# MR-71_RE0.net
KiCad netlist of a schematic drawn in Altium Designer
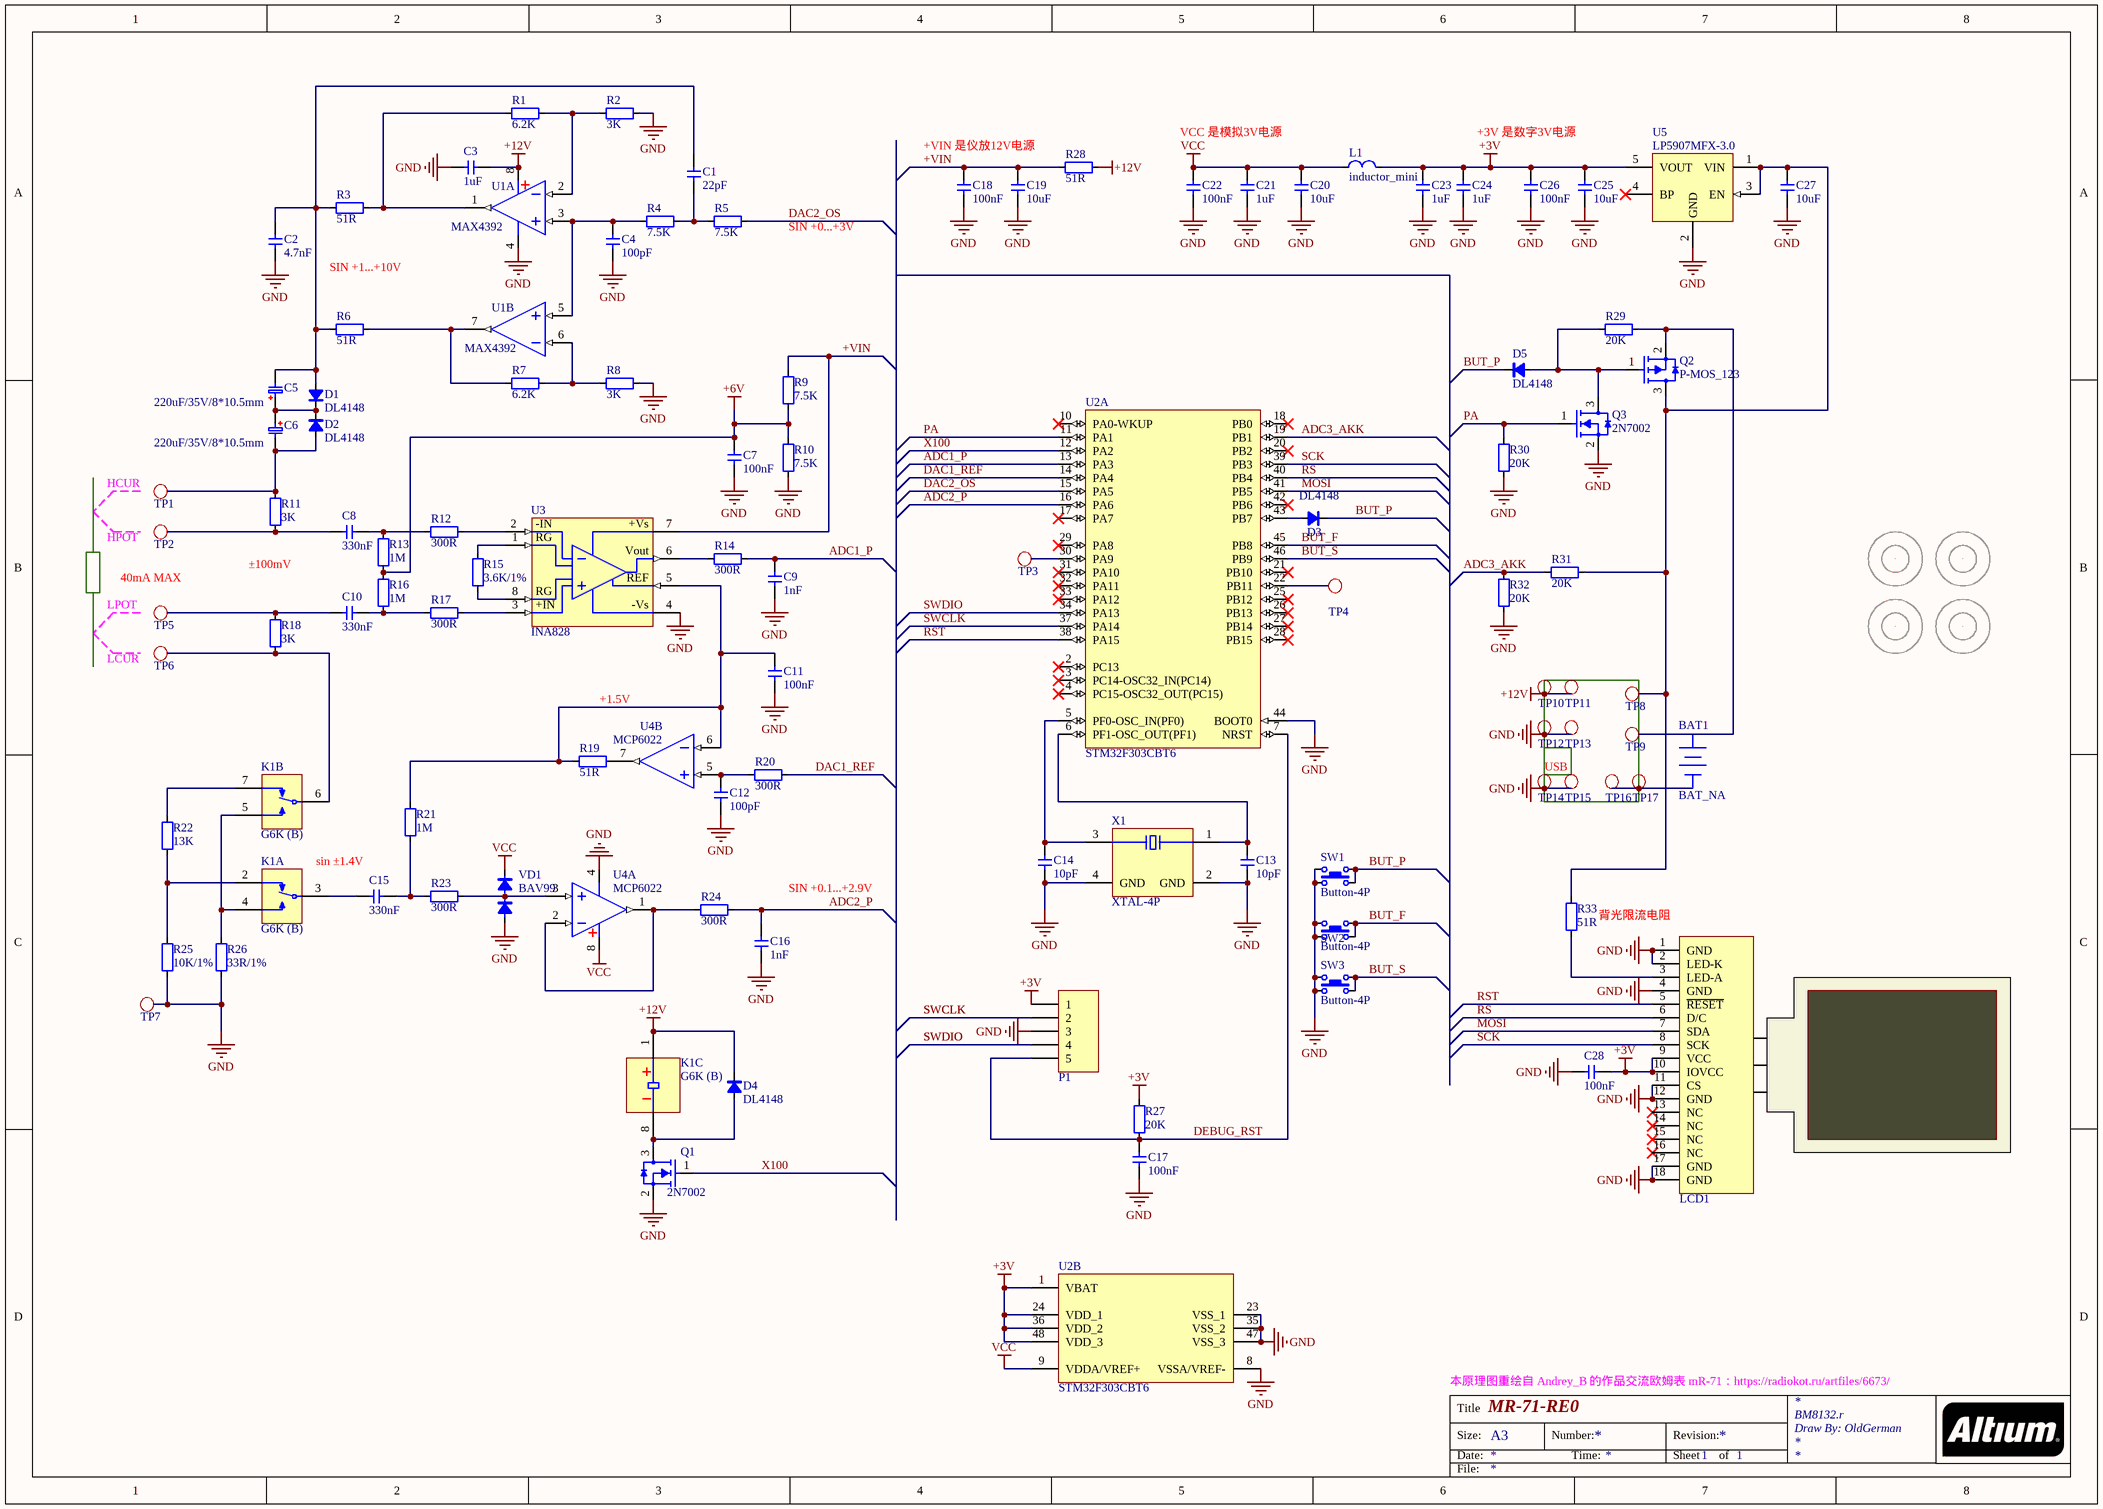
[diagram p0: MR-71_RE0.SchDoc]

(export (version "E")
  (design (tool "Eeschema 10.0.6"))
  (components
    (comp (ref "BAT1")
      (value "BAT_NA")
      (footprint "Lipo_NONE")
      (description "锂电池")
      (libsource (lib "ODG_AD_Lib") (part "BAT_NA"))
    )
    (comp (ref "C1")
      (value "22pF")
      (footprint "C0805")
      (description "Capacitor")
      (libsource (lib "ODG_AD_Lib") (part "CAP"))
    )
    (comp (ref "C2")
      (value "4.7nF")
      (footprint "C0805")
      (description "Capacitor")
      (libsource (lib "ODG_AD_Lib") (part "CAP"))
    )
    (comp (ref "C3")
      (value "1uF")
      (footprint "C0805")
      (description "Capacitor")
      (libsource (lib "ODG_AD_Lib") (part "CAP"))
    )
    (comp (ref "C4")
      (value "100pF")
      (footprint "C0805")
      (description "Capacitor")
      (libsource (lib "ODG_AD_Lib") (part "CAP"))
    )
    (comp (ref "C5")
      (value "220uF/35V/8*10.5mm")
      (footprint "CAP OS-CON D=8.0 L=11.9 E12")
      (description "Capacitor")
      (libsource (lib "ODG_AD_Lib") (part "CAP_Polar_Aluminum"))
    )
    (comp (ref "C6")
      (value "220uF/35V/8*10.5mm")
      (footprint "CAP OS-CON D=8.0 L=11.9 E12")
      (description "Capacitor")
      (libsource (lib "ODG_AD_Lib") (part "CAP_Polar_Aluminum"))
    )
    (comp (ref "C7")
      (value "100nF")
      (footprint "C0805")
      (description "Capacitor")
      (libsource (lib "ODG_AD_Lib") (part "CAP"))
    )
    (comp (ref "C8")
      (value "330nF")
      (footprint "C0805")
      (description "Capacitor")
      (libsource (lib "ODG_AD_Lib") (part "CAP"))
    )
    (comp (ref "C9")
      (value "1nF")
      (footprint "C0805")
      (description "Capacitor")
      (libsource (lib "ODG_AD_Lib") (part "CAP"))
    )
    (comp (ref "C10")
      (value "330nF")
      (footprint "C0805")
      (description "Capacitor")
      (libsource (lib "ODG_AD_Lib") (part "CAP"))
    )
    (comp (ref "C11")
      (value "100nF")
      (footprint "C0805")
      (description "Capacitor")
      (libsource (lib "ODG_AD_Lib") (part "CAP"))
    )
    (comp (ref "C12")
      (value "100pF")
      (footprint "C0805")
      (description "Capacitor")
      (libsource (lib "ODG_AD_Lib") (part "CAP"))
    )
    (comp (ref "C13")
      (value "10pF")
      (footprint "C0805")
      (description "Capacitor")
      (libsource (lib "ODG_AD_Lib") (part "CAP"))
    )
    (comp (ref "C14")
      (value "10pF")
      (footprint "C0805")
      (description "Capacitor")
      (libsource (lib "ODG_AD_Lib") (part "CAP"))
    )
    (comp (ref "C15")
      (value "330nF")
      (footprint "C0805")
      (description "Capacitor")
      (libsource (lib "ODG_AD_Lib") (part "CAP"))
    )
    (comp (ref "C16")
      (value "1nF")
      (footprint "C0805")
      (description "Capacitor")
      (libsource (lib "ODG_AD_Lib") (part "CAP"))
    )
    (comp (ref "C17")
      (value "100nF")
      (footprint "C0805")
      (description "Capacitor")
      (libsource (lib "ODG_AD_Lib") (part "CAP"))
    )
    (comp (ref "C18")
      (value "100nF")
      (footprint "C0805")
      (description "Capacitor")
      (libsource (lib "ODG_AD_Lib") (part "CAP"))
    )
    (comp (ref "C19")
      (value "10uF")
      (footprint "C1206")
      (description "Capacitor")
      (libsource (lib "ODG_AD_Lib") (part "CAP"))
    )
    (comp (ref "C20")
      (value "10uF")
      (footprint "C1206")
      (description "Capacitor")
      (libsource (lib "ODG_AD_Lib") (part "CAP"))
    )
    (comp (ref "C21")
      (value "1uF")
      (footprint "C0805")
      (description "Capacitor")
      (libsource (lib "ODG_AD_Lib") (part "CAP"))
    )
    (comp (ref "C22")
      (value "100nF")
      (footprint "C0805")
      (description "Capacitor")
      (libsource (lib "ODG_AD_Lib") (part "CAP"))
    )
    (comp (ref "C23")
      (value "1uF")
      (footprint "C0805")
      (description "Capacitor")
      (libsource (lib "ODG_AD_Lib") (part "CAP"))
    )
    (comp (ref "C24")
      (value "1uF")
      (footprint "C0805")
      (description "Capacitor")
      (libsource (lib "ODG_AD_Lib") (part "CAP"))
    )
    (comp (ref "C25")
      (value "10uF")
      (footprint "C1206")
      (description "Capacitor")
      (libsource (lib "ODG_AD_Lib") (part "CAP"))
    )
    (comp (ref "C26")
      (value "100nF")
      (footprint "C0805")
      (description "Capacitor")
      (libsource (lib "ODG_AD_Lib") (part "CAP"))
    )
    (comp (ref "C27")
      (value "10uF")
      (footprint "C1206")
      (description "Capacitor")
      (libsource (lib "ODG_AD_Lib") (part "CAP"))
    )
    (comp (ref "C28")
      (value "100nF")
      (footprint "C0805")
      (description "Capacitor")
      (libsource (lib "ODG_AD_Lib") (part "CAP"))
    )
    (comp (ref "D1")
      (value "DL4148")
      (footprint "SOD-123")
      (description "二极管")
      (libsource (lib "ODG_AD_Lib") (part "DIODE"))
    )
    (comp (ref "D2")
      (value "DL4148")
      (footprint "SOD-123")
      (description "二极管")
      (libsource (lib "") (part "DIODE_3"))
    )
    (comp (ref "D3")
      (value "DL4148")
      (footprint "SOD-123")
      (description "二极管")
      (libsource (lib "") (part "DIODE_1"))
    )
    (comp (ref "D4")
      (value "DL4148")
      (footprint "SOD-123")
      (description "二极管")
      (libsource (lib "") (part "DIODE_3"))
    )
    (comp (ref "D5")
      (value "DL4148")
      (footprint "SOD-123")
      (description "二极管")
      (libsource (lib "") (part "DIODE_2"))
    )
    (comp (ref "H1") (value "HOLE") (footprint "M3.1 D=5.8 SUN") (libsource (lib "ODG_AD_Lib") (part "HOLE")))
    (comp (ref "H2") (value "HOLE") (footprint "M3.1 D=5.8 SUN") (libsource (lib "ODG_AD_Lib") (part "HOLE")))
    (comp (ref "H3") (value "HOLE") (footprint "M3.1 D=5.8 SUN") (libsource (lib "ODG_AD_Lib") (part "HOLE")))
    (comp (ref "H4") (value "HOLE") (footprint "M3.1 D=5.8 SUN") (libsource (lib "ODG_AD_Lib") (part "HOLE")))
    (comp (ref "K1")
      (value "G6K (B)")
      (footprint "RELAY_G6K-2F-Y")
      (description "Telecom Relay DPDT (2 Form C) Surface Mount")
      (fields (field (name "MF") "Omron Electronics") (field (name "MP") "G6K-2F DC3"))
      (libsource (lib "") (part "G6K (B)_1"))
    )
    (comp (ref "L1")
      (value "inductor_mini")
      (footprint "FER0805")
      (description "贴片叠层电感")
      (libsource (lib "ODG_AD_Lib") (part "inductor_mini"))
    )
    (comp (ref "LCD1")
      (value "LCD_Universal_128x160_18pin")
      (footprint "LCD-128X160-1.8INCH_SOLDER_MR-71")
      (libsource (lib "ODG_AD_Lib") (part "LCD_Universal_128x160_18pin"))
    )
    (comp (ref "P1")
      (value "CONN_X5")
      (footprint "2.54MM_MALE_X5")
      (libsource (lib "ODG_AD_Lib") (part "CONN_X5"))
    )
    (comp (ref "Q1")
      (value "2N7002")
      (footprint "INFINEON SOT-23-3")
      (description "N-MOS")
      (libsource (lib "ODG_AD_Lib") (part "N-MOS_123"))
    )
    (comp (ref "Q2")
      (value "P-MOS_123")
      (footprint "INFINEON SOT-23-3")
      (description "P-MOS")
      (libsource (lib "ODG_AD_Lib") (part "P-MOS_123"))
    )
    (comp (ref "Q3")
      (value "2N7002")
      (footprint "INFINEON SOT-23-3")
      (description "N-MOS")
      (libsource (lib "ODG_AD_Lib") (part "N-MOS_123"))
    )
    (comp (ref "R1")
      (value "6.2K")
      (footprint "R0805")
      (description "IEC Standard")
      (libsource (lib "") (part "RES_1"))
    )
    (comp (ref "R2")
      (value "3K")
      (footprint "R0805")
      (description "IEC Standard")
      (libsource (lib "") (part "RES_1"))
    )
    (comp (ref "R3")
      (value "51R")
      (footprint "R0805")
      (description "IEC Standard")
      (libsource (lib "") (part "RES_1"))
    )
    (comp (ref "R4")
      (value "7.5K")
      (footprint "R0805")
      (description "IEC Standard")
      (libsource (lib "") (part "RES_1"))
    )
    (comp (ref "R5")
      (value "7.5K")
      (footprint "R0805")
      (description "IEC Standard")
      (libsource (lib "") (part "RES_1"))
    )
    (comp (ref "R6")
      (value "51R")
      (footprint "R0805")
      (description "IEC Standard")
      (libsource (lib "") (part "RES_2"))
    )
    (comp (ref "R7")
      (value "6.2K")
      (footprint "R0805")
      (description "IEC Standard")
      (libsource (lib "") (part "RES_2"))
    )
    (comp (ref "R8")
      (value "3K")
      (footprint "R0805")
      (description "IEC Standard")
      (libsource (lib "") (part "RES_2"))
    )
    (comp (ref "R9")
      (value "7.5K")
      (footprint "R0805")
      (description "IEC Standard")
      (libsource (lib "") (part "RES_2"))
    )
    (comp (ref "R10")
      (value "7.5K")
      (footprint "R0805")
      (description "IEC Standard")
      (libsource (lib "") (part "RES_2"))
    )
    (comp (ref "R11")
      (value "3K")
      (footprint "R0805")
      (description "IEC Standard")
      (libsource (lib "ODG_AD_Lib") (part "RES"))
    )
    (comp (ref "R12")
      (value "300R")
      (footprint "R0805")
      (description "IEC Standard")
      (libsource (lib "") (part "RES_3"))
    )
    (comp (ref "R13")
      (value "1M")
      (footprint "R0805")
      (description "IEC Standard")
      (libsource (lib "ODG_AD_Lib") (part "RES"))
    )
    (comp (ref "R14")
      (value "300R")
      (footprint "R0805")
      (description "IEC Standard")
      (libsource (lib "") (part "RES_3"))
    )
    (comp (ref "R15")
      (value "3.6K/1%")
      (footprint "R0805")
      (description "IEC Standard")
      (libsource (lib "ODG_AD_Lib") (part "RES"))
    )
    (comp (ref "R16")
      (value "1M")
      (footprint "R0805")
      (description "IEC Standard")
      (libsource (lib "ODG_AD_Lib") (part "RES"))
    )
    (comp (ref "R17")
      (value "300R")
      (footprint "R0805")
      (description "IEC Standard")
      (libsource (lib "") (part "RES_3"))
    )
    (comp (ref "R18")
      (value "3K")
      (footprint "R0805")
      (description "IEC Standard")
      (libsource (lib "ODG_AD_Lib") (part "RES"))
    )
    (comp (ref "R19")
      (value "51R")
      (footprint "R0805")
      (description "IEC Standard")
      (libsource (lib "") (part "RES_2"))
    )
    (comp (ref "R20")
      (value "300R")
      (footprint "R0805")
      (description "IEC Standard")
      (libsource (lib "") (part "RES_3"))
    )
    (comp (ref "R21")
      (value "1M")
      (footprint "R0805")
      (description "IEC Standard")
      (libsource (lib "ODG_AD_Lib") (part "RES"))
    )
    (comp (ref "R22")
      (value "13K")
      (footprint "R0805")
      (description "IEC Standard")
      (libsource (lib "ODG_AD_Lib") (part "RES"))
    )
    (comp (ref "R23")
      (value "300R")
      (footprint "R0805")
      (description "IEC Standard")
      (libsource (lib "") (part "RES_3"))
    )
    (comp (ref "R24")
      (value "300R")
      (footprint "R0805")
      (description "IEC Standard")
      (libsource (lib "") (part "RES_3"))
    )
    (comp (ref "R25")
      (value "10K/1%")
      (footprint "R0805")
      (description "IEC Standard")
      (libsource (lib "ODG_AD_Lib") (part "RES"))
    )
    (comp (ref "R26")
      (value "33R/1%")
      (footprint "R1206")
      (description "IEC Standard")
      (libsource (lib "ODG_AD_Lib") (part "RES"))
    )
    (comp (ref "R27")
      (value "20K")
      (footprint "R0805")
      (description "IEC Standard")
      (libsource (lib "") (part "RES_1"))
    )
    (comp (ref "R28")
      (value "51R")
      (footprint "R0805")
      (description "IEC Standard")
      (libsource (lib "") (part "RES_2"))
    )
    (comp (ref "R29")
      (value "20K")
      (footprint "R0805")
      (description "IEC Standard")
      (libsource (lib "") (part "RES_2"))
    )
    (comp (ref "R30")
      (value "20K")
      (footprint "R0805")
      (description "IEC Standard")
      (libsource (lib "ODG_AD_Lib") (part "RES"))
    )
    (comp (ref "R31")
      (value "20K")
      (footprint "R0805")
      (description "IEC Standard")
      (libsource (lib "") (part "RES_2"))
    )
    (comp (ref "R32")
      (value "20K")
      (footprint "R0805")
      (description "IEC Standard")
      (libsource (lib "ODG_AD_Lib") (part "RES"))
    )
    (comp (ref "R33")
      (value "51R")
      (footprint "R0805")
      (description "IEC Standard")
      (libsource (lib "") (part "RES_1"))
    )
    (comp (ref "SW1")
      (value "Button-4P")
      (footprint "TACTILE_SWITCH_SMD_4X4MM")
      (description "Button")
      (libsource (lib "ODG_AD_Lib") (part "Button-4P"))
    )
    (comp (ref "SW2")
      (value "Button-4P")
      (footprint "TACTILE_SWITCH_SMD_4X4MM")
      (description "Button")
      (libsource (lib "ODG_AD_Lib") (part "Button-4P"))
    )
    (comp (ref "SW3")
      (value "Button-4P")
      (footprint "TACTILE_SWITCH_SMD_4X4MM")
      (description "Button")
      (libsource (lib "ODG_AD_Lib") (part "Button-4P"))
    )
    (comp (ref "TP1")
      (value "TP_SMD")
      (footprint "TP_SMD_1.5mm_01")
      (description "SMD testpad")
      (libsource (lib "ODG_AD_Lib") (part "TP_SMD"))
    )
    (comp (ref "TP2")
      (value "TP_SMD")
      (footprint "TP_SMD_1.5mm_01")
      (description "SMD testpad")
      (libsource (lib "ODG_AD_Lib") (part "TP_SMD"))
    )
    (comp (ref "TP3")
      (value "TP_SMD")
      (footprint "TP_SMD_1.5mm_01")
      (description "SMD testpad")
      (libsource (lib "ODG_AD_Lib") (part "TP_SMD"))
    )
    (comp (ref "TP4")
      (value "TP_SMD")
      (footprint "TP_SMD_1.5mm_01")
      (description "SMD testpad")
      (libsource (lib "ODG_AD_Lib") (part "TP_SMD"))
    )
    (comp (ref "TP5")
      (value "TP_SMD")
      (footprint "TP_SMD_1.5mm_01")
      (description "SMD testpad")
      (libsource (lib "ODG_AD_Lib") (part "TP_SMD"))
    )
    (comp (ref "TP6")
      (value "TP_SMD")
      (footprint "TP_SMD_1.5mm_01")
      (description "SMD testpad")
      (libsource (lib "ODG_AD_Lib") (part "TP_SMD"))
    )
    (comp (ref "TP7")
      (value "TP_SMD")
      (footprint "TP_SMD_1.5mm_01")
      (description "SMD testpad")
      (libsource (lib "ODG_AD_Lib") (part "TP_SMD"))
    )
    (comp (ref "TP8")
      (value "TP_SMD")
      (footprint "TP_SMD_1.5mm_01")
      (description "SMD testpad")
      (libsource (lib "ODG_AD_Lib") (part "TP_SMD"))
    )
    (comp (ref "TP9")
      (value "TP_SMD")
      (footprint "TP_SMD_1.5mm_01")
      (description "SMD testpad")
      (libsource (lib "ODG_AD_Lib") (part "TP_SMD"))
    )
    (comp (ref "TP10")
      (value "TP_SMD")
      (footprint "KEYSTONE_5015")
      (description "SMD testpad")
      (libsource (lib "ODG_AD_Lib") (part "TP_SMD"))
    )
    (comp (ref "TP11")
      (value "TP_SMD")
      (footprint "KEYSTONE_5015")
      (description "SMD testpad")
      (libsource (lib "ODG_AD_Lib") (part "TP_SMD"))
    )
    (comp (ref "TP12")
      (value "TP_SMD")
      (footprint "KEYSTONE_5015")
      (description "SMD testpad")
      (libsource (lib "ODG_AD_Lib") (part "TP_SMD"))
    )
    (comp (ref "TP13")
      (value "TP_SMD")
      (footprint "KEYSTONE_5015")
      (description "SMD testpad")
      (libsource (lib "ODG_AD_Lib") (part "TP_SMD"))
    )
    (comp (ref "TP14")
      (value "TP_SMD")
      (footprint "KEYSTONE_5015")
      (description "SMD testpad")
      (libsource (lib "ODG_AD_Lib") (part "TP_SMD"))
    )
    (comp (ref "TP15")
      (value "TP_SMD")
      (footprint "KEYSTONE_5015")
      (description "SMD testpad")
      (libsource (lib "ODG_AD_Lib") (part "TP_SMD"))
    )
    (comp (ref "TP16")
      (value "TP_SMD")
      (footprint "KEYSTONE_5015")
      (description "SMD testpad")
      (libsource (lib "ODG_AD_Lib") (part "TP_SMD"))
    )
    (comp (ref "TP17")
      (value "TP_SMD")
      (footprint "KEYSTONE_5015")
      (description "SMD testpad")
      (libsource (lib "ODG_AD_Lib") (part "TP_SMD"))
    )
    (comp (ref "U1")
      (value "MAX4392")
      (footprint "ANALOG DEV SOIC-8 R8")
      (description "通用型CMOS双路轨到轨放大器\r\nGeneral-Purpose CMOS Dual Rail-to-Rail Amplifier")
      (libsource (lib "ODG_AD_Lib") (part "AD8542"))
    )
    (comp (ref "U2")
      (value "STM32F303CBT6")
      (footprint "ST LQFP-48 7x7MM")
      (description "带DSP和FPU的主流混合信号ARM Cortex-M4 MCU，具有128 KB Flash、72 MHz CPU、MPU、CCM、5 MSPS 12位ADC、PGA和比较器")
      (fields (field (name "PARTNUMBER") "STM32F103CBT6"))
      (libsource (lib "ODG_AD_Lib") (part "STM32F303CBT6"))
    )
    (comp (ref "U3")
      (value "INA828")
      (footprint "ANALOG DEV SOIC-8 R8")
      (description "50-µV Offset, 7-nV/√Hz Noise, Low-Power, Precision Instrumentation Amplifier")
      (libsource (lib "ODG_AD_Lib") (part "INA828"))
    )
    (comp (ref "U4")
      (value "MCP6022")
      (footprint "ANALOG DEV SOIC-8 R8")
      (libsource (lib "ODG_AD_Lib") (part "AD8542"))
    )
    (comp (ref "U5")
      (value "LP5907MFX-3.0")
      (footprint "ANALOG TSOT-23-5 UJ-5")
      (description "超低噪声线性稳压芯片")
      (libsource (lib "ODG_AD_Lib") (part "ADP150AUJZ-3.3-R7"))
    )
    (comp (ref "VD1")
      (value "BAV99")
      (footprint "INFINEON SOT-23-3")
      (description "Dual Series Switching Diodes")
      (libsource (lib "ODG_AD_Lib") (part "BAV99"))
    )
    (comp (ref "X1")
      (value "XTAL-4P")
      (footprint "EPSON TSX-3225")
      (description "4脚无源石英晶振")
      (libsource (lib "ODG_AD_Lib") (part "XTAL-4P_crystal"))
    )
  )
  (nets
    (net (code "1") (name "+3V") (class "Default")
      (node (ref "C23") (pin "1") (pinfunction "1_1") (pintype "passive"))
      (node (ref "C24") (pin "1") (pinfunction "1_1") (pintype "passive"))
      (node (ref "C25") (pin "1") (pinfunction "1_1") (pintype "passive"))
      (node (ref "C26") (pin "1") (pinfunction "1_1") (pintype "passive"))
      (node (ref "C28") (pin "2") (pinfunction "2_2") (pintype "passive"))
      (node (ref "L1") (pin "2") (pinfunction "2_2") (pintype "passive"))
      (node (ref "LCD1") (pin "10") (pinfunction "IOVCC_10") (pintype "passive"))
      (node (ref "LCD1") (pin "9") (pinfunction "VCC_9") (pintype "passive"))
      (node (ref "P1") (pin "1") (pinfunction "1_1") (pintype "passive"))
      (node (ref "R27") (pin "2") (pinfunction "2_2") (pintype "passive"))
      (node (ref "U2") (pin "1") (pinfunction "VBAT_1") (pintype "power_in"))
      (node (ref "U2") (pin "24") (pinfunction "VDD_1_24") (pintype "power_in"))
      (node (ref "U2") (pin "36") (pinfunction "VDD_2_36") (pintype "power_in"))
      (node (ref "U2") (pin "48") (pinfunction "VDD_3_48") (pintype "power_in"))
      (node (ref "U5") (pin "5") (pinfunction "VOUT_5") (pintype "passive"))
    )
    (net (code "2") (name "+6V") (class "Default")
      (node (ref "C7") (pin "1") (pinfunction "1_1") (pintype "passive"))
      (node (ref "R10") (pin "2") (pinfunction "2_2") (pintype "passive"))
      (node (ref "R13") (pin "2") (pinfunction "2_2") (pintype "passive"))
      (node (ref "R16") (pin "1") (pinfunction "1_1") (pintype "passive"))
      (node (ref "R9") (pin "1") (pinfunction "1_1") (pintype "passive"))
    )
    (net (code "3") (name "+12V") (class "Default")
      (node (ref "C3") (pin "2") (pinfunction "2_2") (pintype "passive"))
      (node (ref "D4") (pin "2") (pinfunction "C_2") (pintype "passive"))
      (node (ref "K1") (pin "1") (pinfunction "1_1") (pintype "passive"))
      (node (ref "R28") (pin "2") (pinfunction "2_2") (pintype "passive"))
      (node (ref "TP10") (pin "1") (pinfunction "1_1") (pintype "passive"))
      (node (ref "TP11") (pin "1") (pinfunction "1_1") (pintype "passive"))
      (node (ref "U1") (pin "8") (pinfunction "V+_8") (pintype "power_in"))
    )
    (net (code "4") (name "/+VIN") (class "Default")
      (node (ref "C18") (pin "1") (pinfunction "1_1") (pintype "passive"))
      (node (ref "C19") (pin "1") (pinfunction "1_1") (pintype "passive"))
      (node (ref "R28") (pin "1") (pinfunction "1_1") (pintype "passive"))
      (node (ref "R9") (pin "2") (pinfunction "2_2") (pintype "passive"))
      (node (ref "U3") (pin "7") (pinfunction "+Vs_7") (pintype "passive"))
    )
    (net (code "5") (name "/ADC1_P") (class "Default")
      (node (ref "C9") (pin "1") (pinfunction "1_1") (pintype "passive"))
      (node (ref "R14") (pin "1") (pinfunction "1_1") (pintype "passive"))
      (node (ref "U2") (pin "13") (pinfunction "PA3_13") (pintype "bidirectional"))
    )
    (net (code "6") (name "/ADC2_P") (class "Default")
      (node (ref "C16") (pin "2") (pinfunction "2_2") (pintype "passive"))
      (node (ref "R24") (pin "1") (pinfunction "1_1") (pintype "passive"))
      (node (ref "U2") (pin "16") (pinfunction "PA6_16") (pintype "bidirectional"))
    )
    (net (code "7") (name "/ADC3_AKK") (class "Default")
      (node (ref "R31") (pin "1") (pinfunction "1_1") (pintype "passive"))
      (node (ref "R32") (pin "1") (pinfunction "1_1") (pintype "passive"))
      (node (ref "U2") (pin "19") (pinfunction "PB1_19") (pintype "bidirectional"))
    )
    (net (code "8") (name "/BUT_F") (class "Default")
      (node (ref "SW2") (pin "3") (pinfunction "3_3") (pintype "passive"))
      (node (ref "SW2") (pin "4") (pinfunction "4_4") (pintype "passive"))
      (node (ref "U2") (pin "45") (pinfunction "PB8_45") (pintype "bidirectional"))
    )
    (net (code "9") (name "/BUT_P") (class "Default")
      (node (ref "D3") (pin "2") (pinfunction "C_2") (pintype "passive"))
      (node (ref "D5") (pin "2") (pinfunction "C_2") (pintype "passive"))
      (node (ref "SW1") (pin "3") (pinfunction "3_3") (pintype "passive"))
      (node (ref "SW1") (pin "4") (pinfunction "4_4") (pintype "passive"))
    )
    (net (code "10") (name "/BUT_S") (class "Default")
      (node (ref "SW3") (pin "3") (pinfunction "3_3") (pintype "passive"))
      (node (ref "SW3") (pin "4") (pinfunction "4_4") (pintype "passive"))
      (node (ref "U2") (pin "46") (pinfunction "PB9_46") (pintype "bidirectional"))
    )
    (net (code "11") (name "/DAC1_REF") (class "Default")
      (node (ref "R20") (pin "1") (pinfunction "1_1") (pintype "passive"))
      (node (ref "U2") (pin "14") (pinfunction "PA4_14") (pintype "bidirectional"))
    )
    (net (code "12") (name "/DAC2_OS") (class "Default")
      (node (ref "R5") (pin "2") (pinfunction "2_2") (pintype "passive"))
      (node (ref "U2") (pin "15") (pinfunction "PA5_15") (pintype "bidirectional"))
    )
    (net (code "13") (name "/DEBUG_RST") (class "Default")
      (node (ref "C17") (pin "2") (pinfunction "2_2") (pintype "passive"))
      (node (ref "P1") (pin "5") (pinfunction "5_5") (pintype "passive"))
      (node (ref "R27") (pin "1") (pinfunction "1_1") (pintype "passive"))
      (node (ref "U2") (pin "7") (pinfunction "NRST_7") (pintype "bidirectional"))
    )
    (net (code "14") (name "/MOSI") (class "Default")
      (node (ref "LCD1") (pin "7") (pinfunction "SDA_7") (pintype "passive"))
      (node (ref "U2") (pin "41") (pinfunction "PB5_41") (pintype "bidirectional"))
    )
    (net (code "15") (name "/PA") (class "Default")
      (node (ref "Q3") (pin "1") (pinfunction "G_1") (pintype "passive"))
      (node (ref "R30") (pin "1") (pinfunction "1_1") (pintype "passive"))
      (node (ref "U2") (pin "11") (pinfunction "PA1_11") (pintype "bidirectional"))
    )
    (net (code "16") (name "/RS") (class "Default")
      (node (ref "LCD1") (pin "6") (pinfunction "D/C_6") (pintype "passive"))
      (node (ref "U2") (pin "40") (pinfunction "PB4_40") (pintype "bidirectional"))
    )
    (net (code "17") (name "/RST") (class "Default")
      (node (ref "LCD1") (pin "5") (pinfunction "~{RESET}_5") (pintype "passive"))
      (node (ref "U2") (pin "38") (pinfunction "PA15_38") (pintype "bidirectional"))
    )
    (net (code "18") (name "/SCK") (class "Default")
      (node (ref "LCD1") (pin "8") (pinfunction "SCK_8") (pintype "passive"))
      (node (ref "U2") (pin "39") (pinfunction "PB3_39") (pintype "bidirectional"))
    )
    (net (code "19") (name "/SWCLK") (class "Default")
      (node (ref "P1") (pin "2") (pinfunction "2_2") (pintype "passive"))
      (node (ref "U2") (pin "37") (pinfunction "PA14_37") (pintype "bidirectional"))
    )
    (net (code "20") (name "/SWDIO") (class "Default")
      (node (ref "P1") (pin "4") (pinfunction "4_4") (pintype "passive"))
      (node (ref "U2") (pin "34") (pinfunction "PA13_34") (pintype "bidirectional"))
    )
    (net (code "21") (name "/X100") (class "Default")
      (node (ref "Q1") (pin "1") (pinfunction "G_1") (pintype "passive"))
      (node (ref "U2") (pin "12") (pinfunction "PA2_12") (pintype "bidirectional"))
    )
    (net (code "22") (name "GND") (class "Default")
      (node (ref "C11") (pin "2") (pinfunction "2_2") (pintype "passive"))
      (node (ref "C12") (pin "2") (pinfunction "2_2") (pintype "passive"))
      (node (ref "C13") (pin "1") (pinfunction "1_1") (pintype "passive"))
      (node (ref "C14") (pin "1") (pinfunction "1_1") (pintype "passive"))
      (node (ref "C16") (pin "1") (pinfunction "1_1") (pintype "passive"))
      (node (ref "C17") (pin "1") (pinfunction "1_1") (pintype "passive"))
      (node (ref "C18") (pin "2") (pinfunction "2_2") (pintype "passive"))
      (node (ref "C19") (pin "2") (pinfunction "2_2") (pintype "passive"))
      (node (ref "C2") (pin "2") (pinfunction "2_2") (pintype "passive"))
      (node (ref "C20") (pin "2") (pinfunction "2_2") (pintype "passive"))
      (node (ref "C21") (pin "2") (pinfunction "2_2") (pintype "passive"))
      (node (ref "C22") (pin "2") (pinfunction "2_2") (pintype "passive"))
      (node (ref "C23") (pin "2") (pinfunction "2_2") (pintype "passive"))
      (node (ref "C24") (pin "2") (pinfunction "2_2") (pintype "passive"))
      (node (ref "C25") (pin "2") (pinfunction "2_2") (pintype "passive"))
      (node (ref "C26") (pin "2") (pinfunction "2_2") (pintype "passive"))
      (node (ref "C27") (pin "2") (pinfunction "2_2") (pintype "passive"))
      (node (ref "C28") (pin "1") (pinfunction "1_1") (pintype "passive"))
      (node (ref "C3") (pin "1") (pinfunction "1_1") (pintype "passive"))
      (node (ref "C4") (pin "2") (pinfunction "2_2") (pintype "passive"))
      (node (ref "C7") (pin "2") (pinfunction "2_2") (pintype "passive"))
      (node (ref "C9") (pin "2") (pinfunction "2_2") (pintype "passive"))
      (node (ref "LCD1") (pin "1") (pinfunction "GND_1") (pintype "passive"))
      (node (ref "LCD1") (pin "11") (pinfunction "CS_11") (pintype "passive"))
      (node (ref "LCD1") (pin "12") (pinfunction "GND_12") (pintype "passive"))
      (node (ref "LCD1") (pin "17") (pinfunction "GND_17") (pintype "passive"))
      (node (ref "LCD1") (pin "18") (pinfunction "GND_18") (pintype "passive"))
      (node (ref "LCD1") (pin "2") (pinfunction "LED-K_2") (pintype "passive"))
      (node (ref "LCD1") (pin "4") (pinfunction "GND_4") (pintype "passive"))
      (node (ref "P1") (pin "3") (pinfunction "3_3") (pintype "passive"))
      (node (ref "Q1") (pin "2") (pinfunction "S_2") (pintype "passive"))
      (node (ref "Q3") (pin "2") (pinfunction "S_2") (pintype "passive"))
      (node (ref "R10") (pin "1") (pinfunction "1_1") (pintype "passive"))
      (node (ref "R2") (pin "2") (pinfunction "2_2") (pintype "passive"))
      (node (ref "R25") (pin "2") (pinfunction "2_2") (pintype "passive"))
      (node (ref "R26") (pin "2") (pinfunction "2_2") (pintype "passive"))
      (node (ref "R30") (pin "2") (pinfunction "2_2") (pintype "passive"))
      (node (ref "R32") (pin "2") (pinfunction "2_2") (pintype "passive"))
      (node (ref "R8") (pin "2") (pinfunction "2_2") (pintype "passive"))
      (node (ref "SW1") (pin "1") (pinfunction "1_1") (pintype "passive"))
      (node (ref "SW1") (pin "2") (pinfunction "2_2") (pintype "passive"))
      (node (ref "SW2") (pin "1") (pinfunction "1_1") (pintype "passive"))
      (node (ref "SW2") (pin "2") (pinfunction "2_2") (pintype "passive"))
      (node (ref "SW3") (pin "1") (pinfunction "1_1") (pintype "passive"))
      (node (ref "SW3") (pin "2") (pinfunction "2_2") (pintype "passive"))
      (node (ref "TP12") (pin "1") (pinfunction "1_1") (pintype "passive"))
      (node (ref "TP13") (pin "1") (pinfunction "1_1") (pintype "passive"))
      (node (ref "TP14") (pin "1") (pinfunction "1_1") (pintype "passive"))
      (node (ref "TP15") (pin "1") (pinfunction "1_1") (pintype "passive"))
      (node (ref "TP7") (pin "1") (pinfunction "1_1") (pintype "passive"))
      (node (ref "U1") (pin "4") (pinfunction "V-_4") (pintype "power_in"))
      (node (ref "U2") (pin "23") (pinfunction "VSS_1_23") (pintype "power_in"))
      (node (ref "U2") (pin "35") (pinfunction "VSS_2_35") (pintype "power_in"))
      (node (ref "U2") (pin "44") (pinfunction "BOOT0_44") (pintype "input"))
      (node (ref "U2") (pin "47") (pinfunction "VSS_3_47") (pintype "power_in"))
      (node (ref "U2") (pin "8") (pinfunction "VSSA/VREF-_8") (pintype "power_in"))
      (node (ref "U3") (pin "4") (pinfunction "-Vs_4") (pintype "passive"))
      (node (ref "U4") (pin "4") (pinfunction "V-_4") (pintype "power_in"))
      (node (ref "U5") (pin "2") (pinfunction "GND_2") (pintype "passive"))
      (node (ref "VD1") (pin "1") (pinfunction "1_1") (pintype "passive"))
      (node (ref "X1") (pin "2") (pinfunction "GND_2") (pintype "passive"))
      (node (ref "X1") (pin "4") (pinfunction "GND_4") (pintype "passive"))
    )
    (net (code "23") (name "Net-(C1-Pad2)") (class "Default")
      (node (ref "C1") (pin "2") (pinfunction "2_2") (pintype "passive"))
      (node (ref "R4") (pin "2") (pinfunction "2_2") (pintype "passive"))
      (node (ref "R5") (pin "1") (pinfunction "1_1") (pintype "passive"))
    )
    (net (code "24") (name "Net-(C8-Pad1)") (class "Default")
      (node (ref "C8") (pin "1") (pinfunction "1_1") (pintype "passive"))
      (node (ref "R12") (pin "2") (pinfunction "2_2") (pintype "passive"))
      (node (ref "R13") (pin "1") (pinfunction "1_1") (pintype "passive"))
    )
    (net (code "25") (name "Net-(C8-Pad2)") (class "Default")
      (node (ref "C8") (pin "2") (pinfunction "2_2") (pintype "passive"))
      (node (ref "R11") (pin "2") (pinfunction "2_2") (pintype "passive"))
      (node (ref "TP2") (pin "1") (pinfunction "1_1") (pintype "passive"))
    )
    (net (code "26") (name "Net-(C10-Pad1)") (class "Default")
      (node (ref "C10") (pin "1") (pinfunction "1_1") (pintype "passive"))
      (node (ref "R16") (pin "2") (pinfunction "2_2") (pintype "passive"))
      (node (ref "R17") (pin "2") (pinfunction "2_2") (pintype "passive"))
    )
    (net (code "27") (name "Net-(C10-Pad2)") (class "Default")
      (node (ref "C10") (pin "2") (pinfunction "2_2") (pintype "passive"))
      (node (ref "R18") (pin "1") (pinfunction "1_1") (pintype "passive"))
      (node (ref "TP5") (pin "1") (pinfunction "1_1") (pintype "passive"))
    )
    (net (code "28") (name "Net-(C15-Pad1)") (class "Default")
      (node (ref "C15") (pin "1") (pinfunction "1_1") (pintype "passive"))
      (node (ref "R21") (pin "2") (pinfunction "2_2") (pintype "passive"))
      (node (ref "R23") (pin "2") (pinfunction "2_2") (pintype "passive"))
    )
    (net (code "29") (name "Net-(C15-Pad2)") (class "Default")
      (node (ref "C15") (pin "2") (pinfunction "2_2") (pintype "passive"))
      (node (ref "K1") (pin "3") (pinfunction "3_3") (pintype "passive"))
    )
    (net (code "30") (name "Net-(D1-A)") (class "Default")
      (node (ref "C1") (pin "1") (pinfunction "1_1") (pintype "passive"))
      (node (ref "C2") (pin "1") (pinfunction "1_1") (pintype "passive"))
      (node (ref "C5") (pin "2") (pinfunction "2_2") (pintype "passive"))
      (node (ref "D1") (pin "1") (pinfunction "A_1") (pintype "passive"))
      (node (ref "R3") (pin "1") (pinfunction "1_1") (pintype "passive"))
      (node (ref "R6") (pin "1") (pinfunction "1_1") (pintype "passive"))
    )
    (net (code "31") (name "Net-(D1-C)") (class "Default")
      (node (ref "C5") (pin "1") (pinfunction "1_1") (pintype "passive"))
      (node (ref "C6") (pin "1") (pinfunction "1_1") (pintype "passive"))
      (node (ref "D1") (pin "2") (pinfunction "C_2") (pintype "passive"))
      (node (ref "D2") (pin "2") (pinfunction "C_2") (pintype "passive"))
    )
    (net (code "32") (name "Net-(D2-A)") (class "Default")
      (node (ref "C6") (pin "2") (pinfunction "2_2") (pintype "passive"))
      (node (ref "D2") (pin "1") (pinfunction "A_1") (pintype "passive"))
      (node (ref "R11") (pin "1") (pinfunction "1_1") (pintype "passive"))
      (node (ref "TP1") (pin "1") (pinfunction "1_1") (pintype "passive"))
    )
    (net (code "33") (name "Net-(D3-A)") (class "Default")
      (node (ref "D3") (pin "1") (pinfunction "A_1") (pintype "passive"))
      (node (ref "U2") (pin "43") (pinfunction "PB7_43") (pintype "bidirectional"))
    )
    (net (code "34") (name "Net-(D4-A)") (class "Default")
      (node (ref "D4") (pin "1") (pinfunction "A_1") (pintype "passive"))
      (node (ref "K1") (pin "8") (pinfunction "8_8") (pintype "passive"))
      (node (ref "Q1") (pin "3") (pinfunction "D_3") (pintype "passive"))
    )
    (net (code "35") (name "Net-(D5-A)") (class "Default")
      (node (ref "D5") (pin "1") (pinfunction "A_1") (pintype "passive"))
      (node (ref "Q2") (pin "1") (pinfunction "G_1") (pintype "passive"))
      (node (ref "Q3") (pin "3") (pinfunction "D_3") (pintype "passive"))
      (node (ref "R29") (pin "1") (pinfunction "1_1") (pintype "passive"))
    )
    (net (code "36") (name "Net-(K1-Pad2)") (class "Default")
      (node (ref "K1") (pin "2") (pinfunction "2_2") (pintype "passive"))
      (node (ref "R22") (pin "2") (pinfunction "2_2") (pintype "passive"))
      (node (ref "R25") (pin "1") (pinfunction "1_1") (pintype "passive"))
    )
    (net (code "37") (name "Net-(K1-Pad4)") (class "Default")
      (node (ref "K1") (pin "4") (pinfunction "4_4") (pintype "passive"))
      (node (ref "K1") (pin "5") (pinfunction "5_5") (pintype "passive"))
      (node (ref "R26") (pin "1") (pinfunction "1_1") (pintype "passive"))
    )
    (net (code "38") (name "Net-(K1-Pad6)") (class "Default")
      (node (ref "K1") (pin "6") (pinfunction "6_6") (pintype "passive"))
      (node (ref "R18") (pin "2") (pinfunction "2_2") (pintype "passive"))
      (node (ref "TP6") (pin "1") (pinfunction "1_1") (pintype "passive"))
    )
    (net (code "39") (name "Net-(K1-Pad7)") (class "Default")
      (node (ref "K1") (pin "7") (pinfunction "7_7") (pintype "passive"))
      (node (ref "R22") (pin "1") (pinfunction "1_1") (pintype "passive"))
    )
    (net (code "40") (name "Net-(LCD1-LED-A)") (class "Default")
      (node (ref "LCD1") (pin "3") (pinfunction "LED-A_3") (pintype "passive"))
      (node (ref "R33") (pin "1") (pinfunction "1_1") (pintype "passive"))
    )
    (net (code "41") (name "Net-(Q2-D)") (class "Default")
      (node (ref "C27") (pin "1") (pinfunction "1_1") (pintype "passive"))
      (node (ref "Q2") (pin "3") (pinfunction "D_3") (pintype "passive"))
      (node (ref "R31") (pin "2") (pinfunction "2_2") (pintype "passive"))
      (node (ref "R33") (pin "2") (pinfunction "2_2") (pintype "passive"))
      (node (ref "TP8") (pin "1") (pinfunction "1_1") (pintype "passive"))
      (node (ref "U5") (pin "1") (pinfunction "VIN_1") (pintype "passive"))
      (node (ref "U5") (pin "3") (pinfunction "EN_3") (pintype "input"))
    )
    (net (code "42") (name "Net-(Q2-S)") (class "Default")
      (node (ref "Q2") (pin "2") (pinfunction "S_2") (pintype "passive"))
      (node (ref "R29") (pin "2") (pinfunction "2_2") (pintype "passive"))
      (node (ref "TP9") (pin "1") (pinfunction "1_1") (pintype "passive"))
    )
    (net (code "43") (name "Net-(R15-Pad1)") (class "Default")
      (node (ref "R15") (pin "1") (pinfunction "1_1") (pintype "passive"))
      (node (ref "U3") (pin "1") (pinfunction "RG_1") (pintype "input"))
    )
    (net (code "44") (name "Net-(R15-Pad2)") (class "Default")
      (node (ref "R15") (pin "2") (pinfunction "2_2") (pintype "passive"))
      (node (ref "U3") (pin "8") (pinfunction "RG_8") (pintype "input"))
    )
    (net (code "45") (name "Net-(TP16-Pad1)") (class "Default")
      (node (ref "TP16") (pin "1") (pinfunction "1_1") (pintype "passive"))
      (node (ref "TP17") (pin "1") (pinfunction "1_1") (pintype "passive"))
    )
    (net (code "46") (name "Net-(U1A-+)") (class "Default")
      (node (ref "C4") (pin "1") (pinfunction "1_1") (pintype "passive"))
      (node (ref "R4") (pin "1") (pinfunction "1_1") (pintype "passive"))
      (node (ref "U1") (pin "3") (pinfunction "+_3") (pintype "input"))
      (node (ref "U1") (pin "5") (pinfunction "+_5") (pintype "input"))
    )
    (net (code "47") (name "Net-(U1A--)") (class "Default")
      (node (ref "R1") (pin "2") (pinfunction "2_2") (pintype "passive"))
      (node (ref "R2") (pin "1") (pinfunction "1_1") (pintype "passive"))
      (node (ref "U1") (pin "2") (pinfunction "-_2") (pintype "input"))
    )
    (net (code "48") (name "Net-(U1A-OUT1)") (class "Default")
      (node (ref "R1") (pin "1") (pinfunction "1_1") (pintype "passive"))
      (node (ref "R3") (pin "2") (pinfunction "2_2") (pintype "passive"))
      (node (ref "U1") (pin "1") (pinfunction "OUT1_1") (pintype "output"))
    )
    (net (code "49") (name "Net-(U1B--)") (class "Default")
      (node (ref "R7") (pin "2") (pinfunction "2_2") (pintype "passive"))
      (node (ref "R8") (pin "1") (pinfunction "1_1") (pintype "passive"))
      (node (ref "U1") (pin "6") (pinfunction "-_6") (pintype "input"))
    )
    (net (code "50") (name "Net-(U1B-OUT2)") (class "Default")
      (node (ref "R6") (pin "2") (pinfunction "2_2") (pintype "passive"))
      (node (ref "R7") (pin "1") (pinfunction "1_1") (pintype "passive"))
      (node (ref "U1") (pin "7") (pinfunction "OUT2_7") (pintype "output"))
    )
    (net (code "51") (name "Net-(U2A-PA9)") (class "Default")
      (node (ref "TP3") (pin "1") (pinfunction "1_1") (pintype "passive"))
      (node (ref "U2") (pin "30") (pinfunction "PA9_30") (pintype "bidirectional"))
    )
    (net (code "52") (name "Net-(U2A-PB11)") (class "Default")
      (node (ref "TP4") (pin "1") (pinfunction "1_1") (pintype "passive"))
      (node (ref "U2") (pin "22") (pinfunction "PB11_22") (pintype "bidirectional"))
    )
    (net (code "53") (name "Net-(U2A-PF0-OSC_IN(PF0))") (class "Default")
      (node (ref "C14") (pin "2") (pinfunction "2_2") (pintype "passive"))
      (node (ref "U2") (pin "5") (pinfunction "PF0-OSC_IN(PF0)_5") (pintype "bidirectional"))
      (node (ref "X1") (pin "3") (pinfunction "3_3") (pintype "passive"))
    )
    (net (code "54") (name "Net-(U2A-PF1-OSC_OUT(PF1))") (class "Default")
      (node (ref "C13") (pin "2") (pinfunction "2_2") (pintype "passive"))
      (node (ref "U2") (pin "6") (pinfunction "PF1-OSC_OUT(PF1)_6") (pintype "bidirectional"))
      (node (ref "X1") (pin "1") (pinfunction "1_1") (pintype "passive"))
    )
    (net (code "55") (name "Net-(U3-+IN)") (class "Default")
      (node (ref "R17") (pin "1") (pinfunction "1_1") (pintype "passive"))
      (node (ref "U3") (pin "3") (pinfunction "+IN_3") (pintype "input"))
    )
    (net (code "56") (name "Net-(U3--IN)") (class "Default")
      (node (ref "R12") (pin "1") (pinfunction "1_1") (pintype "passive"))
      (node (ref "U3") (pin "2") (pinfunction "-IN_2") (pintype "input"))
    )
    (net (code "57") (name "Net-(U3-REF)") (class "Default")
      (node (ref "C11") (pin "1") (pinfunction "1_1") (pintype "passive"))
      (node (ref "R19") (pin "1") (pinfunction "1_1") (pintype "passive"))
      (node (ref "R21") (pin "1") (pinfunction "1_1") (pintype "passive"))
      (node (ref "U3") (pin "5") (pinfunction "REF_5") (pintype "input"))
      (node (ref "U4") (pin "6") (pinfunction "-_6") (pintype "input"))
    )
    (net (code "58") (name "Net-(U3-Vout)") (class "Default")
      (node (ref "R14") (pin "2") (pinfunction "2_2") (pintype "passive"))
      (node (ref "U3") (pin "6") (pinfunction "Vout_6") (pintype "output"))
    )
    (net (code "59") (name "Net-(U4A-+)") (class "Default")
      (node (ref "R23") (pin "1") (pinfunction "1_1") (pintype "passive"))
      (node (ref "U4") (pin "3") (pinfunction "+_3") (pintype "input"))
      (node (ref "VD1") (pin "3") (pinfunction "3_3") (pintype "passive"))
    )
    (net (code "60") (name "Net-(U4A--)") (class "Default")
      (node (ref "R24") (pin "2") (pinfunction "2_2") (pintype "passive"))
      (node (ref "U4") (pin "1") (pinfunction "OUT1_1") (pintype "output"))
      (node (ref "U4") (pin "2") (pinfunction "-_2") (pintype "input"))
    )
    (net (code "61") (name "Net-(U4B-+)") (class "Default")
      (node (ref "C12") (pin "1") (pinfunction "1_1") (pintype "passive"))
      (node (ref "R20") (pin "2") (pinfunction "2_2") (pintype "passive"))
      (node (ref "U4") (pin "5") (pinfunction "+_5") (pintype "input"))
    )
    (net (code "62") (name "Net-(U4B-OUT2)") (class "Default")
      (node (ref "R19") (pin "2") (pinfunction "2_2") (pintype "passive"))
      (node (ref "U4") (pin "7") (pinfunction "OUT2_7") (pintype "output"))
    )
    (net (code "63") (name "VCC") (class "Default")
      (node (ref "C20") (pin "1") (pinfunction "1_1") (pintype "passive"))
      (node (ref "C21") (pin "1") (pinfunction "1_1") (pintype "passive"))
      (node (ref "C22") (pin "1") (pinfunction "1_1") (pintype "passive"))
      (node (ref "L1") (pin "1") (pinfunction "1_1") (pintype "passive"))
      (node (ref "U2") (pin "9") (pinfunction "VDDA/VREF+_9") (pintype "power_in"))
      (node (ref "U4") (pin "8") (pinfunction "V+_8") (pintype "power_in"))
      (node (ref "VD1") (pin "2") (pinfunction "2_2") (pintype "passive"))
    )
    (net (code "64") (name "unconnected-(H1-Pad1)") (class "Default")
      (node (ref "H1") (pin "1") (pinfunction "1_1") (pintype "passive"))
    )
    (net (code "65") (name "unconnected-(H2-Pad1)") (class "Default")
      (node (ref "H2") (pin "1") (pinfunction "1_1") (pintype "passive"))
    )
    (net (code "66") (name "unconnected-(H3-Pad1)") (class "Default")
      (node (ref "H3") (pin "1") (pinfunction "1_1") (pintype "passive"))
    )
    (net (code "67") (name "unconnected-(H4-Pad1)") (class "Default")
      (node (ref "H4") (pin "1") (pinfunction "1_1") (pintype "passive"))
    )
    (net (code "68") (name "unconnected-(LCD1-NC-Pad13)") (class "Default")
      (node (ref "LCD1") (pin "13") (pinfunction "NC_13") (pintype "passive+no_connect"))
    )
    (net (code "69") (name "unconnected-(LCD1-NC-Pad14)") (class "Default")
      (node (ref "LCD1") (pin "14") (pinfunction "NC_14") (pintype "passive+no_connect"))
    )
    (net (code "70") (name "unconnected-(LCD1-NC-Pad15)") (class "Default")
      (node (ref "LCD1") (pin "15") (pinfunction "NC_15") (pintype "passive+no_connect"))
    )
    (net (code "71") (name "unconnected-(LCD1-NC-Pad16)") (class "Default")
      (node (ref "LCD1") (pin "16") (pinfunction "NC_16") (pintype "passive+no_connect"))
    )
    (net (code "72") (name "unconnected-(U2A-PA0-WKUP-Pad10)") (class "Default")
      (node (ref "U2") (pin "10") (pinfunction "PA0-WKUP_10") (pintype "bidirectional+no_connect"))
    )
    (net (code "73") (name "unconnected-(U2A-PA7-Pad17)") (class "Default")
      (node (ref "U2") (pin "17") (pinfunction "PA7_17") (pintype "bidirectional+no_connect"))
    )
    (net (code "74") (name "unconnected-(U2A-PA8-Pad29)") (class "Default")
      (node (ref "U2") (pin "29") (pinfunction "PA8_29") (pintype "bidirectional+no_connect"))
    )
    (net (code "75") (name "unconnected-(U2A-PA10-Pad31)") (class "Default")
      (node (ref "U2") (pin "31") (pinfunction "PA10_31") (pintype "bidirectional+no_connect"))
    )
    (net (code "76") (name "unconnected-(U2A-PA11-Pad32)") (class "Default")
      (node (ref "U2") (pin "32") (pinfunction "PA11_32") (pintype "bidirectional+no_connect"))
    )
    (net (code "77") (name "unconnected-(U2A-PA12-Pad33)") (class "Default")
      (node (ref "U2") (pin "33") (pinfunction "PA12_33") (pintype "bidirectional+no_connect"))
    )
    (net (code "78") (name "unconnected-(U2A-PB0-Pad18)") (class "Default")
      (node (ref "U2") (pin "18") (pinfunction "PB0_18") (pintype "bidirectional+no_connect"))
    )
    (net (code "79") (name "unconnected-(U2A-PB2-Pad20)") (class "Default")
      (node (ref "U2") (pin "20") (pinfunction "PB2_20") (pintype "bidirectional+no_connect"))
    )
    (net (code "80") (name "unconnected-(U2A-PB6-Pad42)") (class "Default")
      (node (ref "U2") (pin "42") (pinfunction "PB6_42") (pintype "bidirectional+no_connect"))
    )
    (net (code "81") (name "unconnected-(U2A-PB10-Pad21)") (class "Default")
      (node (ref "U2") (pin "21") (pinfunction "PB10_21") (pintype "bidirectional+no_connect"))
    )
    (net (code "82") (name "unconnected-(U2A-PB12-Pad25)") (class "Default")
      (node (ref "U2") (pin "25") (pinfunction "PB12_25") (pintype "bidirectional+no_connect"))
    )
    (net (code "83") (name "unconnected-(U2A-PB13-Pad26)") (class "Default")
      (node (ref "U2") (pin "26") (pinfunction "PB13_26") (pintype "bidirectional+no_connect"))
    )
    (net (code "84") (name "unconnected-(U2A-PB14-Pad27)") (class "Default")
      (node (ref "U2") (pin "27") (pinfunction "PB14_27") (pintype "bidirectional+no_connect"))
    )
    (net (code "85") (name "unconnected-(U2A-PB15-Pad28)") (class "Default")
      (node (ref "U2") (pin "28") (pinfunction "PB15_28") (pintype "bidirectional+no_connect"))
    )
    (net (code "86") (name "unconnected-(U2A-PC13-Pad2)") (class "Default")
      (node (ref "U2") (pin "2") (pinfunction "PC13_2") (pintype "bidirectional+no_connect"))
    )
    (net (code "87") (name "unconnected-(U2A-PC14-OSC32_IN(PC14)-Pad3)") (class "Default")
      (node (ref "U2") (pin "3") (pinfunction "PC14-OSC32_IN(PC14)_3") (pintype "bidirectional+no_connect"))
    )
    (net (code "88") (name "unconnected-(U2A-PC15-OSC32_OUT(PC15)-Pad4)") (class "Default")
      (node (ref "U2") (pin "4") (pinfunction "PC15-OSC32_OUT(PC15)_4") (pintype "bidirectional+no_connect"))
    )
    (net (code "89") (name "unconnected-(U5-BP-Pad4)") (class "Default")
      (node (ref "U5") (pin "4") (pinfunction "BP_4") (pintype "passive+no_connect"))
    )
  )
)
